# AT32F437.net
KiCad netlist of a schematic drawn in EasyEDA
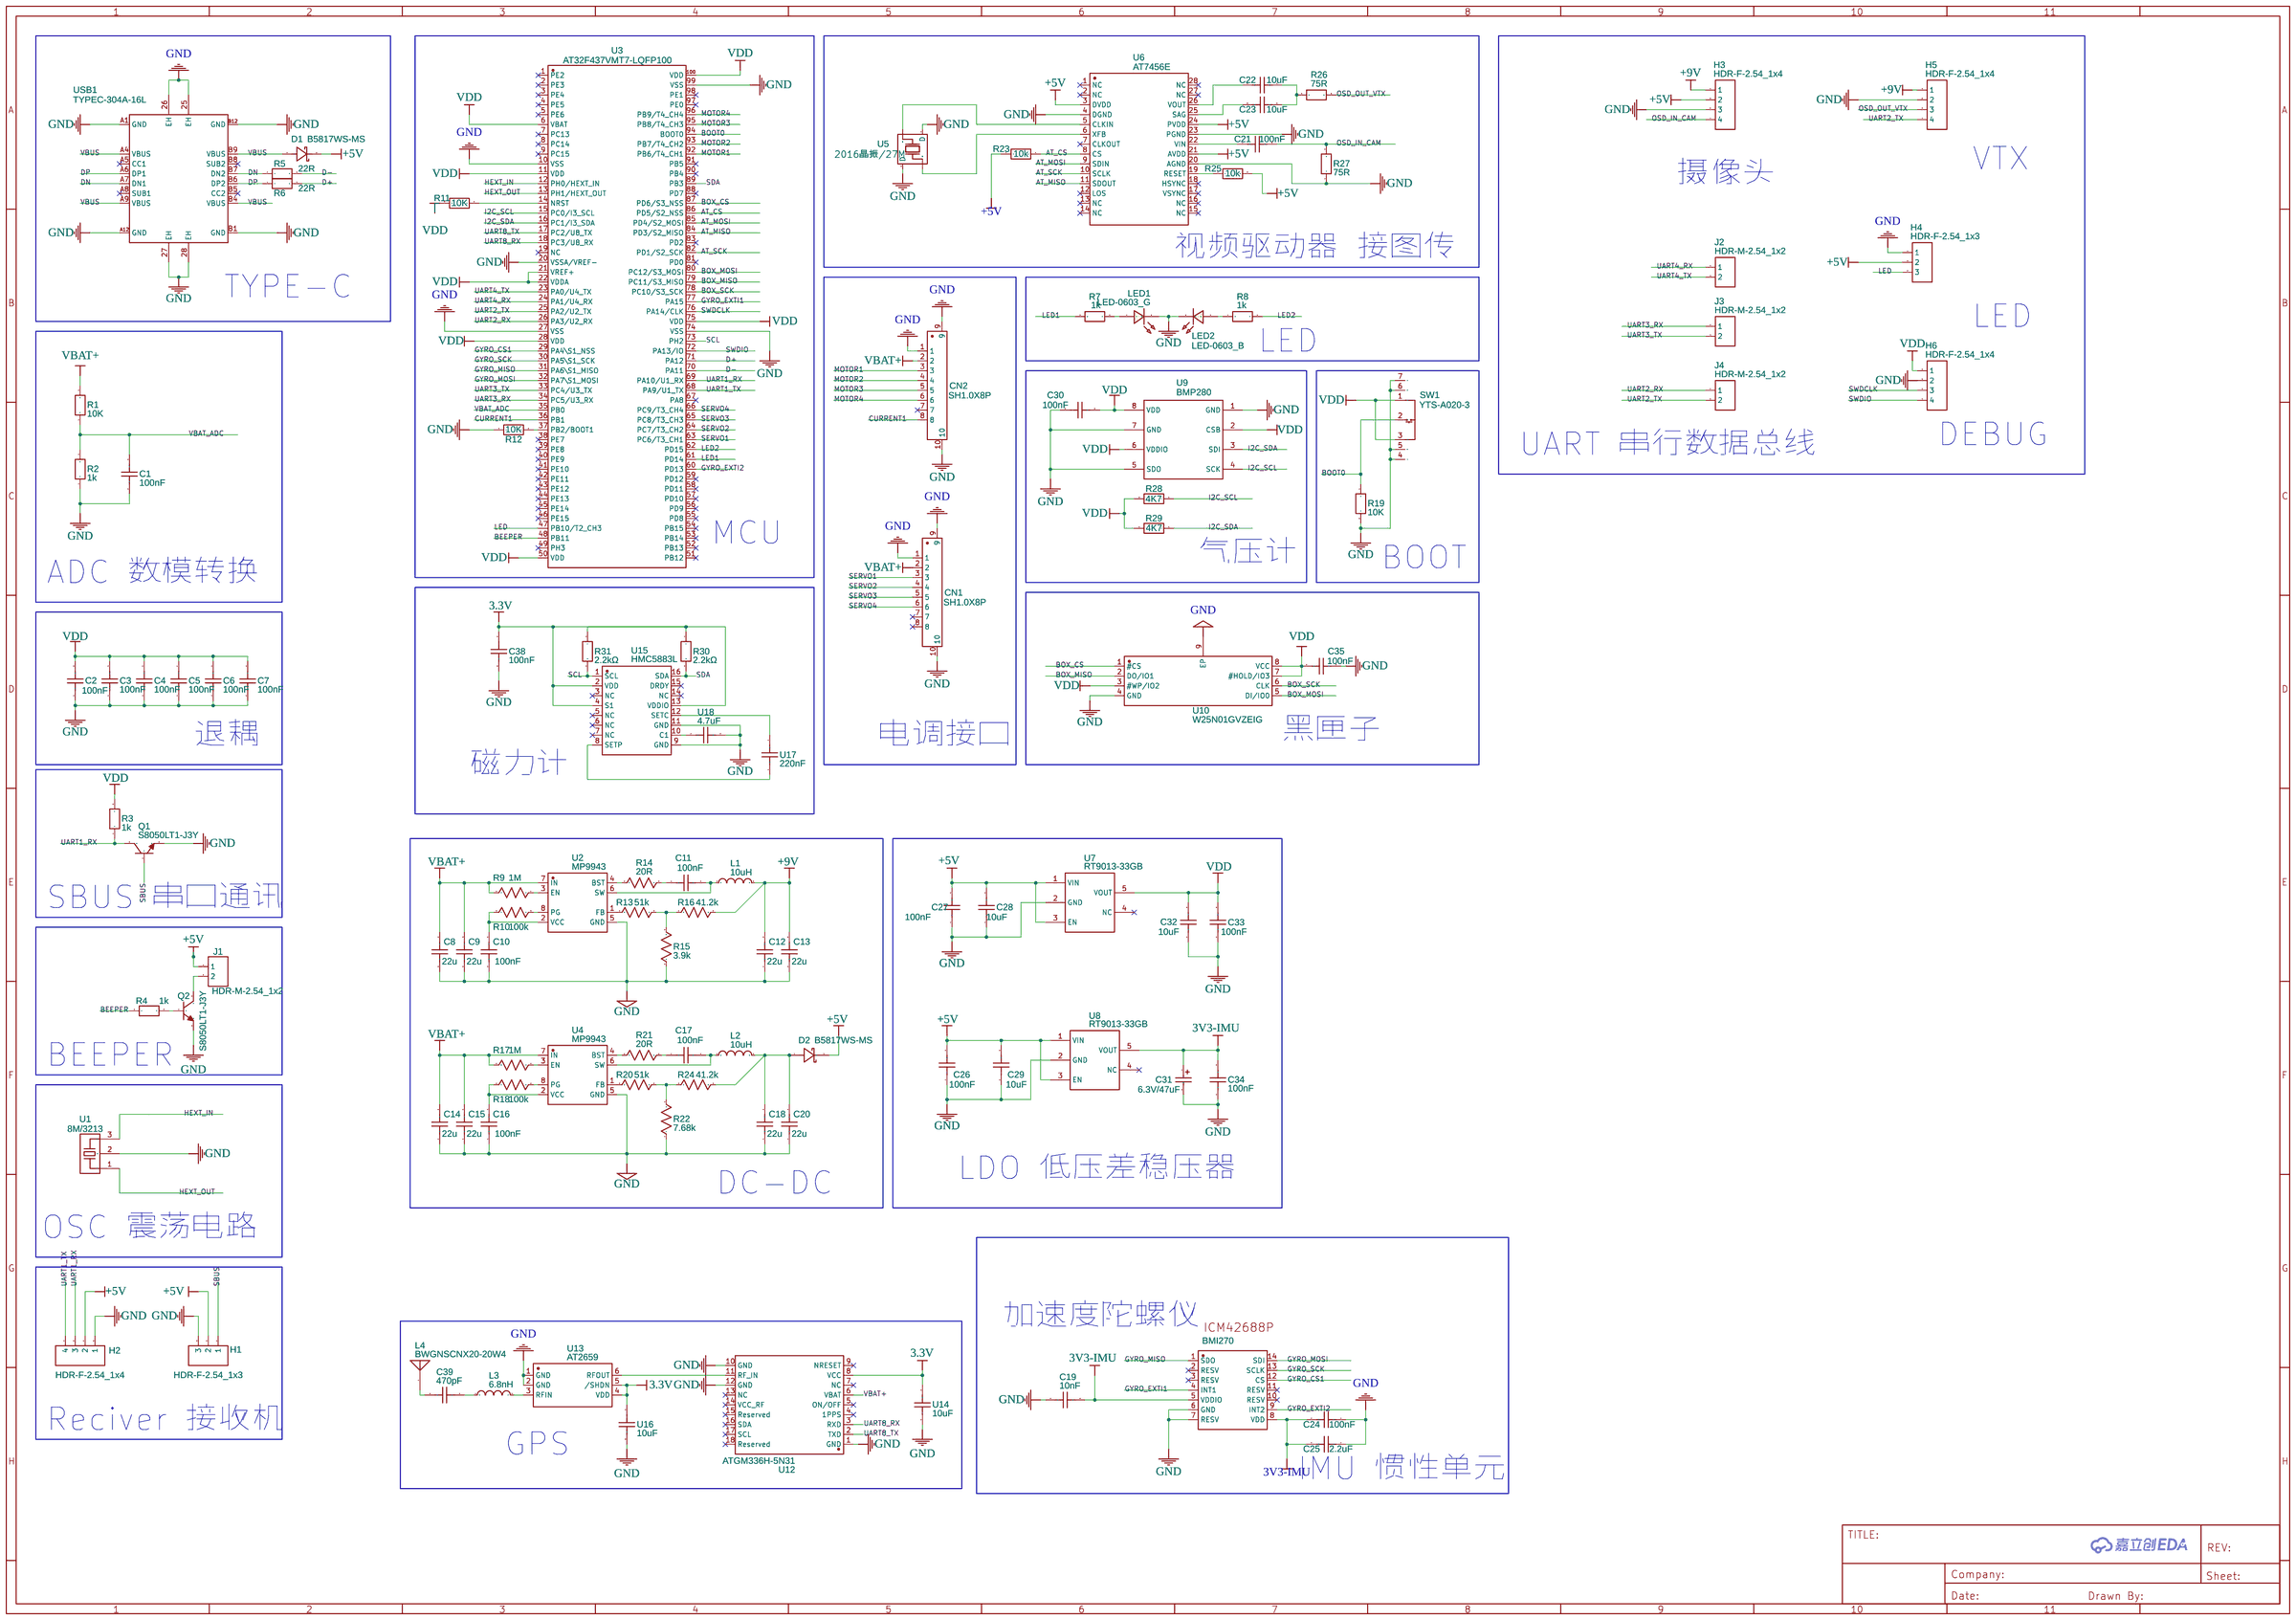
[diagram p0: schematic sheet]

(export (version "E")
  (design (tool "Eeschema 10.0.6"))
  (components
    (comp (ref "C1") (value "100nF") (libsource (lib "") (part "C_0402_US_1")))
    (comp (ref "C2") (value "100nF") (libsource (lib "") (part "C_0402_US_1")))
    (comp (ref "C3") (value "100nF") (libsource (lib "") (part "C_0402_US_1")))
    (comp (ref "C4") (value "100nF") (libsource (lib "") (part "C_0402_US_1")))
    (comp (ref "C5") (value "100nF") (libsource (lib "") (part "C_0402_US_1")))
    (comp (ref "C6") (value "100nF") (libsource (lib "") (part "C_0402_US_1")))
    (comp (ref "C7") (value "100nF") (libsource (lib "") (part "C_0402_US_1")))
    (comp (ref "C8") (value "22u") (libsource (lib "") (part "C_0201_US")))
    (comp (ref "C9") (value "22u") (libsource (lib "") (part "C_0201_US")))
    (comp (ref "C10") (value "100nF") (libsource (lib "") (part "C_0201_US")))
    (comp (ref "C11") (value "100nF") (libsource (lib "") (part "C_0201_US_1")))
    (comp (ref "C12") (value "22u") (libsource (lib "") (part "C_0201_US")))
    (comp (ref "C13") (value "22u") (libsource (lib "") (part "C_0201_US")))
    (comp (ref "C14") (value "22u") (libsource (lib "") (part "C_0201_US")))
    (comp (ref "C15") (value "22u") (libsource (lib "") (part "C_0201_US")))
    (comp (ref "C16") (value "100nF") (libsource (lib "") (part "C_0201_US")))
    (comp (ref "C17") (value "100nF") (libsource (lib "") (part "C_0201_US_1")))
    (comp (ref "C18") (value "22u") (libsource (lib "") (part "C_0201_US")))
    (comp (ref "C19") (value "10nF") (libsource (lib "") (part "C_0402_US_2")))
    (comp (ref "C20") (value "22u") (libsource (lib "") (part "C_0201_US")))
    (comp (ref "C21") (value "100nF") (libsource (lib "") (part "C_0402_US_2")))
    (comp (ref "C22") (value "10uF") (libsource (lib "") (part "C_0603_US")))
    (comp (ref "C23") (value "10uF") (libsource (lib "") (part "C_0603_US")))
    (comp (ref "C24") (value "100nF") (libsource (lib "") (part "C_0402_US")))
    (comp (ref "C25") (value "2.2uF") (libsource (lib "") (part "C_0402_US")))
    (comp (ref "C26") (value "100nF") (libsource (lib "") (part "C_0603_US_1")))
    (comp (ref "C27") (value "100nF") (libsource (lib "") (part "C_0603_US_1")))
    (comp (ref "C28") (value "10uF") (libsource (lib "") (part "C_0603_US_1")))
    (comp (ref "C29") (value "10uF") (libsource (lib "") (part "C_0402_US_1")))
    (comp (ref "C30") (value "100nF") (libsource (lib "") (part "C_0402_US_2")))
    (comp (ref "C31")
      (value "6.3V/47uF")
      (fields (field (name "Manufacturer Part") "TAJA476K006RNJ") (field (name "Manufacturer") "AVX"))
      (libsource (lib "") (part "TAJA476K006RNJ"))
    )
    (comp (ref "C32") (value "10uF") (libsource (lib "") (part "C_0603_US_1")))
    (comp (ref "C33") (value "100nF") (libsource (lib "") (part "C_0603_US_1")))
    (comp (ref "C34") (value "100nF") (libsource (lib "") (part "C_0402_US_1")))
    (comp (ref "C35") (value "100nF") (libsource (lib "") (part "C_0402_US_2")))
    (comp (ref "C38")
      (value "100nF")
      (fields
        (field (name "Manufacturer Part") "CC0603MRY5V8BB104")
        (field (name "Manufacturer") "YAGEO(国巨)")
      )
      (libsource (lib "") (part "CC0603MRY5V8BB104"))
    )
    (comp (ref "C39")
      (value "470pF")
      (fields (field (name "Manufacturer Part") "FM18X471K101PSG") (field (name "Manufacturer") "PSA(信昌电陶)"))
      (libsource (lib "") (part "FM18X471K101PSG"))
    )
    (comp (ref "CN1")
      (value "SH1.0X8P")
      (fields (field (name "Manufacturer Part") "WAFER_SMT_1.0X8"))
      (libsource (lib "") (part "WAFER_SMT_1.0X8"))
    )
    (comp (ref "CN2")
      (value "SH1.0X8P")
      (fields (field (name "Manufacturer Part") "WAFER_SMT_1.0X8"))
      (libsource (lib "") (part "WAFER_SMT_1.0X8"))
    )
    (comp (ref "D1")
      (value "B5817WS-MS")
      (fields (field (name "Manufacturer") "MSKSEMI(美森科)"))
      (libsource (lib "") (part "B5817WS-MS"))
    )
    (comp (ref "D2")
      (value "B5817WS-MS")
      (fields (field (name "Manufacturer") "MSKSEMI(美森科)"))
      (libsource (lib "") (part "B5817WS-MS"))
    )
    (comp (ref "H1") (value "HDR-F-2.54_1x3") (libsource (lib "") (part "HDR-F-2.54_1x3")))
    (comp (ref "H2") (value "HDR-F-2.54_1x4") (libsource (lib "") (part "HDR-F-2.54_1x4")))
    (comp (ref "H3") (value "HDR-F-2.54_1x4") (libsource (lib "") (part "HDR-F-2.54_1x4_1")))
    (comp (ref "H4") (value "HDR-F-2.54_1x3") (libsource (lib "") (part "HDR-F-2.54_1x3_1")))
    (comp (ref "H5") (value "HDR-F-2.54_1x4") (libsource (lib "") (part "HDR-F-2.54_1x4_1")))
    (comp (ref "H6") (value "HDR-F-2.54_1x4") (libsource (lib "") (part "HDR-F-2.54_1x4_1")))
    (comp (ref "J1") (value "HDR-M-2.54_1x2") (libsource (lib "") (part "HDR-M-2.54_1x2")))
    (comp (ref "J2") (value "HDR-M-2.54_1x2") (libsource (lib "") (part "HDR-M-2.54_1x2")))
    (comp (ref "J3") (value "HDR-M-2.54_1x2") (libsource (lib "") (part "HDR-M-2.54_1x2")))
    (comp (ref "J4") (value "HDR-M-2.54_1x2") (libsource (lib "") (part "HDR-M-2.54_1x2")))
    (comp (ref "L1")
      (value "10uH")
      (fields (field (name "Manufacturer Part") "PHC0420-100M-T") (field (name "Manufacturer") "EMTEK"))
      (libsource (lib "") (part "PHC0420-100M-T"))
    )
    (comp (ref "L2")
      (value "10uH")
      (fields (field (name "Manufacturer Part") "PHC0420-100M-T") (field (name "Manufacturer") "EMTEK"))
      (libsource (lib "") (part "PHC0420-100M-T"))
    )
    (comp (ref "L3")
      (value "6.8nH")
      (fields (field (name "Manufacturer Part") "VHF060303H6N8KT") (field (name "Manufacturer") "FH(风华)"))
      (libsource (lib "") (part "VHF060303H6N8KT"))
    )
    (comp (ref "L4")
      (value "BWGNSCNX20-20W4")
      (fields (field (name "Manufacturer") "BAT WIRELESS(蝙蝠无线)"))
      (libsource (lib "") (part "BWGNSCNX20-20W4"))
    )
    (comp (ref "LED1")
      (value "LED-0603_G")
      (fields
        (field (name "Manufacturer Part") "19-217/GHC-YR1S2/3T")
        (field (name "Manufacturer") "EVERLIGHT(台湾亿光)")
      )
      (libsource (lib "") (part "LED-0603_G"))
    )
    (comp (ref "LED2")
      (value "LED-0603_B")
      (fields
        (field (name "Manufacturer Part") "19-217/BHC-ZL1M2RY/3T")
        (field (name "Manufacturer") "EVERLIGHT(台湾亿光)")
      )
      (libsource (lib "") (part "LED-0603_B"))
    )
    (comp (ref "Q1")
      (value "S8050LT1-J3Y")
      (fields (field (name "Manufacturer") "FH(风华)"))
      (libsource (lib "") (part "S8050LT1-J3Y_1"))
    )
    (comp (ref "Q2")
      (value "S8050LT1-J3Y")
      (fields (field (name "Manufacturer") "FH(风华)"))
      (libsource (lib "") (part "S8050LT1-J3Y"))
    )
    (comp (ref "R1") (value "10K") (libsource (lib "") (part "R_0603_EU_2")))
    (comp (ref "R2") (value "1k") (libsource (lib "") (part "R_0603_EU_2")))
    (comp (ref "R3") (value "1k") (libsource (lib "") (part "R_0402_EU_2")))
    (comp (ref "R4") (value "1k") (libsource (lib "") (part "R_0402_EU")))
    (comp (ref "R5") (value "22R") (libsource (lib "") (part "R_0402_EU")))
    (comp (ref "R6") (value "22R") (libsource (lib "") (part "R_0402_EU")))
    (comp (ref "R7") (value "1k") (libsource (lib "") (part "R_0603_EU")))
    (comp (ref "R8") (value "1k") (libsource (lib "") (part "R_0603_EU_3")))
    (comp (ref "R9") (value "1M") (libsource (lib "") (part "R_0201_US_2")))
    (comp (ref "R10") (value "100k") (libsource (lib "") (part "R_0201_US")))
    (comp (ref "R11") (value "10K") (libsource (lib "") (part "R_0603_EU")))
    (comp (ref "R12") (value "10K") (libsource (lib "") (part "R_0603_EU_3")))
    (comp (ref "R13") (value "51k") (libsource (lib "") (part "R_0201_US")))
    (comp (ref "R14") (value "20R") (libsource (lib "") (part "R_0201_US")))
    (comp (ref "R15") (value "3.9k") (libsource (lib "") (part "R_0201_US_1")))
    (comp (ref "R16") (value "41.2k") (libsource (lib "") (part "R_0201_US")))
    (comp (ref "R17") (value "1M") (libsource (lib "") (part "R_0201_US_2")))
    (comp (ref "R18") (value "100k") (libsource (lib "") (part "R_0201_US")))
    (comp (ref "R19") (value "10K") (libsource (lib "") (part "R_0603_EU_1")))
    (comp (ref "R20") (value "51k") (libsource (lib "") (part "R_0201_US")))
    (comp (ref "R21") (value "20R") (libsource (lib "") (part "R_0201_US")))
    (comp (ref "R22") (value "7.68k") (libsource (lib "") (part "R_0201_US_1")))
    (comp (ref "R23") (value "10k") (libsource (lib "") (part "R_0402_EU")))
    (comp (ref "R24") (value "41.2k") (libsource (lib "") (part "R_0201_US")))
    (comp (ref "R25") (value "10k") (libsource (lib "") (part "R_0402_EU")))
    (comp (ref "R26") (value "75R") (libsource (lib "") (part "R_0805_EU")))
    (comp (ref "R27") (value "75R") (libsource (lib "") (part "R_0805_EU_1")))
    (comp (ref "R28") (value "4K7") (libsource (lib "") (part "R_0402_EU_1")))
    (comp (ref "R29") (value "4K7") (libsource (lib "") (part "R_0402_EU_1")))
    (comp (ref "R30")
      (value "2.2kΩ")
      (fields (field (name "Manufacturer Part") "SCR0603J2K2") (field (name "Manufacturer") "VO(翔胜)"))
      (libsource (lib "") (part "SCR0603J2K2"))
    )
    (comp (ref "R31")
      (value "2.2kΩ")
      (fields (field (name "Manufacturer Part") "SCR0603J2K2") (field (name "Manufacturer") "VO(翔胜)"))
      (libsource (lib "") (part "SCR0603J2K2"))
    )
    (comp (ref "SDO1") (value "BMI270") (libsource (lib "") (part "ICM42688-P")))
    (comp (ref "SW1")
      (value "YTS-A020-3")
      (fields (field (name "Manufacturer") "YIYUAN(怡远)"))
      (libsource (lib "") (part "YTS-A020-3"))
    )
    (comp (ref "U1") (value "8M/3213") (libsource (lib "") (part "3213晶振")))
    (comp (ref "U2") (value "MP9943") (libsource (lib "") (part "MP9943")))
    (comp (ref "U3")
      (value "AT32F437VMT7-LQFP100")
      (fields (field (name "Manufacturer Part") "AT32F435VMT7") (field (name "Manufacturer") "ARTERY（雅特力）"))
      (libsource (lib "") (part "AT32F435VGT7"))
    )
    (comp (ref "U4") (value "MP9943") (libsource (lib "") (part "MP9943")))
    (comp (ref "U5") (value "2016晶振/27M") (libsource (lib "") (part "3225晶振")))
    (comp (ref "U6")
      (value "AT7456E")
      (fields (field (name "Manufacturer") "ZHONGKEWEI"))
      (libsource (lib "") (part "AT7456E"))
    )
    (comp (ref "U7")
      (value "RT9013-33GB")
      (fields (field (name "Manufacturer") "RICHTEK"))
      (libsource (lib "") (part "RT9013-33GB"))
    )
    (comp (ref "U8")
      (value "RT9013-33GB")
      (fields (field (name "Manufacturer") "RICHTEK"))
      (libsource (lib "") (part "RT9013-33GB"))
    )
    (comp (ref "U9")
      (value "BMP280")
      (fields (field (name "Manufacturer") "Bosch"))
      (libsource (lib "") (part "BMP280"))
    )
    (comp (ref "U10")
      (value "W25N01GVZEIG")
      (fields (field (name "Manufacturer") "Winbond Elec"))
      (libsource (lib "") (part "W25N01GVZEIG NoHole"))
    )
    (comp (ref "U12")
      (value "ATGM336H-5N31")
      (fields (field (name "Manufacturer") "杭州中科微"))
      (libsource (lib "") (part "ATGM336H-5N31"))
    )
    (comp (ref "U13")
      (value "AT2659")
      (fields (field (name "Manufacturer") "杭州中科微"))
      (libsource (lib "") (part "AT2659"))
    )
    (comp (ref "U14")
      (value "10uF")
      (fields (field (name "Manufacturer Part") "0603X106K100CT") (field (name "Manufacturer") "Walsin(华新科)"))
      (libsource (lib "") (part "0603X106K100CT"))
    )
    (comp (ref "U15") (value "HMC5883L") (libsource (lib "") (part "HMC5883L")))
    (comp (ref "U16")
      (value "10uF")
      (fields (field (name "Manufacturer Part") "0603X106K100CT") (field (name "Manufacturer") "Walsin(华新科)"))
      (libsource (lib "") (part "0603X106K100CT"))
    )
    (comp (ref "U17")
      (value "220nF")
      (fields (field (name "Manufacturer Part") "CGA3E3X5R1V224M080AB") (field (name "Manufacturer") "TDK"))
      (libsource (lib "") (part "CGA3E3X5R1V224M080AB"))
    )
    (comp (ref "U18")
      (value "4.7uF")
      (fields (field (name "Manufacturer Part") "C1005X5R1A475M050BC") (field (name "Manufacturer") "TDK"))
      (libsource (lib "") (part "C1005X5R1A475M050BC"))
    )
    (comp (ref "USB1")
      (value "TYPEC-304A-16L")
      (fields
        (field (name "Manufacturer Part") "TYPEC-304A-ACP16L")
        (field (name "Manufacturer") "XUNPU(讯普)")
      )
      (libsource (lib "") (part "TYPEC-304A-ACP16L"))
    )
  )
  (nets
    (net (code "1") (name "+5V") (class "Default")
      (node (ref "C26") (pin "2") (pinfunction "2_2") (pintype "unspecified"))
      (node (ref "C27") (pin "2") (pinfunction "2_2") (pintype "unspecified"))
      (node (ref "C28") (pin "2") (pinfunction "2_2") (pintype "unspecified"))
      (node (ref "C29") (pin "2") (pinfunction "2_2") (pintype "unspecified"))
      (node (ref "D1") (pin "2") (pinfunction "K_2") (pintype "unspecified"))
      (node (ref "D2") (pin "2") (pinfunction "K_2") (pintype "unspecified"))
      (node (ref "H1") (pin "2") (pinfunction "2_2") (pintype "input"))
      (node (ref "H2") (pin "2") (pinfunction "2_2") (pintype "unspecified"))
      (node (ref "H3") (pin "2") (pinfunction "2_2") (pintype "unspecified"))
      (node (ref "H4") (pin "2") (pinfunction "2_2") (pintype "input"))
      (node (ref "J1") (pin "1") (pinfunction "1_1") (pintype "unspecified"))
      (node (ref "R23") (pin "1") (pinfunction "1_1") (pintype "unspecified"))
      (node (ref "R25") (pin "2") (pinfunction "2_2") (pintype "unspecified"))
      (node (ref "U6") (pin "21") (pinfunction "AVDD_21") (pintype "unspecified"))
      (node (ref "U6") (pin "24") (pinfunction "PVDD_24") (pintype "unspecified"))
      (node (ref "U6") (pin "3") (pinfunction "DVDD_3") (pintype "unspecified"))
      (node (ref "U7") (pin "1") (pinfunction "VIN_1") (pintype "unspecified"))
      (node (ref "U7") (pin "3") (pinfunction "EN_3") (pintype "unspecified"))
      (node (ref "U8") (pin "1") (pinfunction "VIN_1") (pintype "unspecified"))
      (node (ref "U8") (pin "3") (pinfunction "EN_3") (pintype "unspecified"))
    )
    (net (code "2") (name "+9V") (class "Default")
      (node (ref "C12") (pin "2") (pinfunction "2_2") (pintype "unspecified"))
      (node (ref "C13") (pin "2") (pinfunction "2_2") (pintype "unspecified"))
      (node (ref "H3") (pin "1") (pinfunction "1_1") (pintype "unspecified"))
      (node (ref "H5") (pin "1") (pinfunction "1_1") (pintype "unspecified"))
      (node (ref "L1") (pin "2") (pinfunction "2_2") (pintype "unspecified"))
      (node (ref "R16") (pin "2") (pinfunction "2_2") (pintype "unspecified"))
    )
    (net (code "3") (name "/AT_CS") (class "Default")
      (node (ref "R23") (pin "2") (pinfunction "2_2") (pintype "unspecified"))
      (node (ref "U3") (pin "86") (pinfunction "PD5/S2_NSS_86") (pintype "unspecified"))
      (node (ref "U6") (pin "8") (pinfunction "CS_8") (pintype "unspecified"))
    )
    (net (code "4") (name "/AT_MISO") (class "Default")
      (node (ref "U3") (pin "84") (pinfunction "PD3/S2_MISO_84") (pintype "unspecified"))
      (node (ref "U6") (pin "11") (pinfunction "SDOUT_11") (pintype "unspecified"))
    )
    (net (code "5") (name "/AT_MOSI") (class "Default")
      (node (ref "U3") (pin "85") (pinfunction "PD4/S2_MOSI_85") (pintype "unspecified"))
      (node (ref "U6") (pin "9") (pinfunction "SDIN_9") (pintype "unspecified"))
    )
    (net (code "6") (name "/AT_SCK") (class "Default")
      (node (ref "U3") (pin "82") (pinfunction "PD1/S2_SCK_82") (pintype "unspecified"))
      (node (ref "U6") (pin "10") (pinfunction "SCLK_10") (pintype "unspecified"))
    )
    (net (code "7") (name "/BEEPER") (class "Default")
      (node (ref "R4") (pin "1") (pinfunction "1_1") (pintype "unspecified"))
      (node (ref "U3") (pin "48") (pinfunction "PB11_48") (pintype "unspecified"))
    )
    (net (code "8") (name "/BOOT0") (class "Default")
      (node (ref "R19") (pin "1") (pinfunction "1_1") (pintype "unspecified"))
      (node (ref "SW1") (pin "2") (pinfunction "2_2") (pintype "unspecified"))
      (node (ref "U3") (pin "94") (pinfunction "BOOT0_94") (pintype "unspecified"))
    )
    (net (code "9") (name "/BOX_CS") (class "Default")
      (node (ref "U10") (pin "1") (pinfunction "#CS_1") (pintype "unspecified"))
      (node (ref "U3") (pin "87") (pinfunction "PD6/S3_NSS_87") (pintype "unspecified"))
    )
    (net (code "10") (name "/BOX_MISO") (class "Default")
      (node (ref "U10") (pin "2") (pinfunction "DO/IO1_2") (pintype "unspecified"))
      (node (ref "U3") (pin "79") (pinfunction "PC11/S3_MISO_79") (pintype "unspecified"))
    )
    (net (code "11") (name "/BOX_MOSI") (class "Default")
      (node (ref "U10") (pin "5") (pinfunction "DI/IO0_5") (pintype "unspecified"))
      (node (ref "U3") (pin "80") (pinfunction "PC12/S3_MOSI_80") (pintype "unspecified"))
    )
    (net (code "12") (name "/BOX_SCK") (class "Default")
      (node (ref "U10") (pin "6") (pinfunction "CLK_6") (pintype "unspecified"))
      (node (ref "U3") (pin "78") (pinfunction "PC10/S3_SCK_78") (pintype "unspecified"))
    )
    (net (code "13") (name "/CURRENT1") (class "Default")
      (node (ref "CN2") (pin "8") (pinfunction "8_8") (pintype "unspecified"))
      (node (ref "U3") (pin "36") (pinfunction "PB1_36") (pintype "unspecified"))
    )
    (net (code "14") (name "/D+") (class "Default")
      (node (ref "R6") (pin "2") (pinfunction "2_2") (pintype "unspecified"))
      (node (ref "U3") (pin "71") (pinfunction "PA12_71") (pintype "unspecified"))
    )
    (net (code "15") (name "/D-") (class "Default")
      (node (ref "R5") (pin "2") (pinfunction "2_2") (pintype "unspecified"))
      (node (ref "U3") (pin "70") (pinfunction "PA11_70") (pintype "unspecified"))
    )
    (net (code "16") (name "/DN") (class "Default")
      (node (ref "R5") (pin "1") (pinfunction "1_1") (pintype "unspecified"))
      (node (ref "USB1") (pin "A7") (pinfunction "DN1_A7") (pintype "unspecified"))
      (node (ref "USB1") (pin "B7") (pinfunction "DN2_B7") (pintype "unspecified"))
    )
    (net (code "17") (name "/DP") (class "Default")
      (node (ref "R6") (pin "1") (pinfunction "1_1") (pintype "unspecified"))
      (node (ref "USB1") (pin "A6") (pinfunction "DP1_A6") (pintype "unspecified"))
      (node (ref "USB1") (pin "B6") (pinfunction "DP2_B6") (pintype "unspecified"))
    )
    (net (code "18") (name "/GYRO_CS1") (class "Default")
      (node (ref "SDO1") (pin "12") (pinfunction "CS_12") (pintype "unspecified"))
      (node (ref "U3") (pin "29") (pinfunction "PA4\\S1_NSS_29") (pintype "unspecified"))
    )
    (net (code "19") (name "/GYRO_EXTI1") (class "Default")
      (node (ref "SDO1") (pin "4") (pinfunction "INT1_4") (pintype "unspecified"))
      (node (ref "U3") (pin "77") (pinfunction "PA15_77") (pintype "unspecified"))
    )
    (net (code "20") (name "/GYRO_EXTI2") (class "Default")
      (node (ref "SDO1") (pin "9") (pinfunction "INT2_9") (pintype "unspecified"))
      (node (ref "U3") (pin "60") (pinfunction "PD13_60") (pintype "unspecified"))
    )
    (net (code "21") (name "/GYRO_MISO") (class "Default")
      (node (ref "SDO1") (pin "1") (pinfunction "SDO_1") (pintype "unspecified"))
      (node (ref "U3") (pin "31") (pinfunction "PA6\\S1_MISO_31") (pintype "unspecified"))
    )
    (net (code "22") (name "/GYRO_MOSI") (class "Default")
      (node (ref "SDO1") (pin "14") (pinfunction "SDI_14") (pintype "unspecified"))
      (node (ref "U3") (pin "32") (pinfunction "PA7\\S1_MOSI_32") (pintype "unspecified"))
    )
    (net (code "23") (name "/GYRO_SCK") (class "Default")
      (node (ref "SDO1") (pin "13") (pinfunction "SCLK_13") (pintype "unspecified"))
      (node (ref "U3") (pin "30") (pinfunction "PA5\\S1_SCK_30") (pintype "unspecified"))
    )
    (net (code "24") (name "/HEXT_IN") (class "Default")
      (node (ref "U1") (pin "3") (pinfunction "3_3") (pintype "unspecified"))
      (node (ref "U3") (pin "12") (pinfunction "PH0/HEXT_IN_12") (pintype "unspecified"))
    )
    (net (code "25") (name "/HEXT_OUT") (class "Default")
      (node (ref "U1") (pin "1") (pinfunction "1_1") (pintype "unspecified"))
      (node (ref "U3") (pin "13") (pinfunction "PH1/HEXT_OUT_13") (pintype "unspecified"))
    )
    (net (code "26") (name "/I2C_SCL") (class "Default")
      (node (ref "R28") (pin "1") (pinfunction "1_1") (pintype "unspecified"))
      (node (ref "U3") (pin "15") (pinfunction "PC0/I3_SCL_15") (pintype "unspecified"))
      (node (ref "U9") (pin "4") (pinfunction "SCK_4") (pintype "unspecified"))
    )
    (net (code "27") (name "/I2C_SDA") (class "Default")
      (node (ref "R29") (pin "1") (pinfunction "1_1") (pintype "unspecified"))
      (node (ref "U3") (pin "16") (pinfunction "PC1/I3_SDA_16") (pintype "unspecified"))
      (node (ref "U9") (pin "3") (pinfunction "SDI_3") (pintype "unspecified"))
    )
    (net (code "28") (name "/LED") (class "Default")
      (node (ref "H4") (pin "3") (pinfunction "3_3") (pintype "input"))
      (node (ref "U3") (pin "47") (pinfunction "PB10/T2_CH3_47") (pintype "unspecified"))
    )
    (net (code "29") (name "/LED1") (class "Default")
      (node (ref "R7") (pin "2") (pinfunction "2_2") (pintype "unspecified"))
      (node (ref "U3") (pin "61") (pinfunction "PD14_61") (pintype "unspecified"))
    )
    (net (code "30") (name "/LED2") (class "Default")
      (node (ref "R8") (pin "2") (pinfunction "2_2") (pintype "unspecified"))
      (node (ref "U3") (pin "62") (pinfunction "PD15_62") (pintype "unspecified"))
    )
    (net (code "31") (name "/MOTOR1") (class "Default")
      (node (ref "CN2") (pin "3") (pinfunction "3_3") (pintype "unspecified"))
      (node (ref "U3") (pin "92") (pinfunction "PB6/T4_CH1_92") (pintype "unspecified"))
    )
    (net (code "32") (name "/MOTOR2") (class "Default")
      (node (ref "CN2") (pin "4") (pinfunction "4_4") (pintype "unspecified"))
      (node (ref "U3") (pin "93") (pinfunction "PB7/T4_CH2_93") (pintype "unspecified"))
    )
    (net (code "33") (name "/MOTOR3") (class "Default")
      (node (ref "CN2") (pin "5") (pinfunction "5_5") (pintype "unspecified"))
      (node (ref "U3") (pin "95") (pinfunction "PB8/T4_CH3_95") (pintype "unspecified"))
    )
    (net (code "34") (name "/MOTOR4") (class "Default")
      (node (ref "CN2") (pin "6") (pinfunction "6_6") (pintype "unspecified"))
      (node (ref "U3") (pin "96") (pinfunction "PB9/T4_CH4_96") (pintype "unspecified"))
    )
    (net (code "35") (name "/OSD_IN_CAM") (class "Default")
      (node (ref "C21") (pin "2") (pinfunction "2_2") (pintype "unspecified"))
      (node (ref "H3") (pin "4") (pinfunction "4_4") (pintype "unspecified"))
      (node (ref "R27") (pin "2") (pinfunction "2_2") (pintype "unspecified"))
    )
    (net (code "36") (name "/OSD_OUT_VTX") (class "Default")
      (node (ref "H5") (pin "3") (pinfunction "3_3") (pintype "unspecified"))
      (node (ref "R26") (pin "2") (pinfunction "2_2") (pintype "unspecified"))
    )
    (net (code "37") (name "/SBUS") (class "Default")
      (node (ref "H1") (pin "1") (pinfunction "1_1") (pintype "input"))
      (node (ref "Q1") (pin "1") (pinfunction "1_1") (pintype "input"))
    )
    (net (code "38") (name "/SCL") (class "Default")
      (node (ref "R31") (pin "2") (pinfunction "2_2") (pintype "unspecified"))
      (node (ref "U15") (pin "1") (pinfunction "SCL_1") (pintype "unspecified"))
      (node (ref "U3") (pin "73") (pinfunction "PH2_73") (pintype "unspecified"))
    )
    (net (code "39") (name "/SDA") (class "Default")
      (node (ref "R30") (pin "2") (pinfunction "2_2") (pintype "unspecified"))
      (node (ref "U15") (pin "16") (pinfunction "SDA_16") (pintype "unspecified"))
      (node (ref "U3") (pin "89") (pinfunction "PB3_89") (pintype "unspecified"))
    )
    (net (code "40") (name "/SERVO1") (class "Default")
      (node (ref "CN1") (pin "3") (pinfunction "3_3") (pintype "unspecified"))
      (node (ref "U3") (pin "63") (pinfunction "PC6/T3_CH1_63") (pintype "unspecified"))
    )
    (net (code "41") (name "/SERVO2") (class "Default")
      (node (ref "CN1") (pin "4") (pinfunction "4_4") (pintype "unspecified"))
      (node (ref "U3") (pin "64") (pinfunction "PC7/T3_CH2_64") (pintype "unspecified"))
    )
    (net (code "42") (name "/SERVO3") (class "Default")
      (node (ref "CN1") (pin "5") (pinfunction "5_5") (pintype "unspecified"))
      (node (ref "U3") (pin "65") (pinfunction "PC8/T3_CH3_65") (pintype "unspecified"))
    )
    (net (code "43") (name "/SERVO4") (class "Default")
      (node (ref "CN1") (pin "6") (pinfunction "6_6") (pintype "unspecified"))
      (node (ref "U3") (pin "66") (pinfunction "PC9/T3_CH4_66") (pintype "unspecified"))
    )
    (net (code "44") (name "/SWDCLK") (class "Default")
      (node (ref "H6") (pin "3") (pinfunction "3_3") (pintype "unspecified"))
      (node (ref "U3") (pin "76") (pinfunction "PA14/CLK_76") (pintype "unspecified"))
    )
    (net (code "45") (name "/SWDIO") (class "Default")
      (node (ref "H6") (pin "4") (pinfunction "4_4") (pintype "unspecified"))
      (node (ref "U3") (pin "72") (pinfunction "PA13/IO_72") (pintype "unspecified"))
    )
    (net (code "46") (name "/UART1_RX") (class "Default")
      (node (ref "H2") (pin "3") (pinfunction "3_3") (pintype "unspecified"))
      (node (ref "Q1") (pin "3") (pinfunction "3_3") (pintype "input"))
      (node (ref "R3") (pin "1") (pinfunction "1_1") (pintype "unspecified"))
      (node (ref "U3") (pin "69") (pinfunction "PA10/U1_RX_69") (pintype "unspecified"))
    )
    (net (code "47") (name "/UART1_TX") (class "Default")
      (node (ref "H2") (pin "4") (pinfunction "4_4") (pintype "unspecified"))
      (node (ref "U3") (pin "68") (pinfunction "PA9/U1_TX_68") (pintype "unspecified"))
    )
    (net (code "48") (name "/UART2_RX") (class "Default")
      (node (ref "J4") (pin "1") (pinfunction "1_1") (pintype "unspecified"))
      (node (ref "U3") (pin "26") (pinfunction "PA3/U2_RX_26") (pintype "unspecified"))
    )
    (net (code "49") (name "/UART2_TX") (class "Default")
      (node (ref "H5") (pin "4") (pinfunction "4_4") (pintype "unspecified"))
      (node (ref "J4") (pin "2") (pinfunction "2_2") (pintype "unspecified"))
      (node (ref "U3") (pin "25") (pinfunction "PA2/U2_TX_25") (pintype "unspecified"))
    )
    (net (code "50") (name "/UART3_RX") (class "Default")
      (node (ref "J3") (pin "1") (pinfunction "1_1") (pintype "unspecified"))
      (node (ref "U3") (pin "34") (pinfunction "PC5/U3_RX_34") (pintype "unspecified"))
    )
    (net (code "51") (name "/UART3_TX") (class "Default")
      (node (ref "J3") (pin "2") (pinfunction "2_2") (pintype "unspecified"))
      (node (ref "U3") (pin "33") (pinfunction "PC4/U3_TX_33") (pintype "unspecified"))
    )
    (net (code "52") (name "/UART4_RX") (class "Default")
      (node (ref "J2") (pin "1") (pinfunction "1_1") (pintype "unspecified"))
      (node (ref "U3") (pin "24") (pinfunction "PA1/U4_RX_24") (pintype "unspecified"))
    )
    (net (code "53") (name "/UART4_TX") (class "Default")
      (node (ref "J2") (pin "2") (pinfunction "2_2") (pintype "unspecified"))
      (node (ref "U3") (pin "23") (pinfunction "PA0/U4_TX_23") (pintype "unspecified"))
    )
    (net (code "54") (name "/UART8_RX") (class "Default")
      (node (ref "U12") (pin "3") (pinfunction "RXD_3") (pintype "unspecified"))
      (node (ref "U3") (pin "18") (pinfunction "PC3/U8_RX_18") (pintype "unspecified"))
    )
    (net (code "55") (name "/UART8_TX") (class "Default")
      (node (ref "U12") (pin "2") (pinfunction "TXD_2") (pintype "unspecified"))
      (node (ref "U3") (pin "17") (pinfunction "PC2/U8_TX_17") (pintype "unspecified"))
    )
    (net (code "56") (name "/VBAT_ADC") (class "Default")
      (node (ref "C1") (pin "2") (pinfunction "2_2") (pintype "unspecified"))
      (node (ref "R1") (pin "1") (pinfunction "1_1") (pintype "unspecified"))
      (node (ref "R2") (pin "2") (pinfunction "2_2") (pintype "unspecified"))
      (node (ref "U3") (pin "35") (pinfunction "PB0_35") (pintype "unspecified"))
    )
    (net (code "57") (name "/VBUS") (class "Default")
      (node (ref "D1") (pin "1") (pinfunction "A_1") (pintype "unspecified"))
      (node (ref "USB1") (pin "A4") (pinfunction "VBUS_A4") (pintype "unspecified"))
      (node (ref "USB1") (pin "A9") (pinfunction "VBUS_A9") (pintype "unspecified"))
      (node (ref "USB1") (pin "B4") (pinfunction "VBUS_B4") (pintype "unspecified"))
      (node (ref "USB1") (pin "B9") (pinfunction "VBUS_B9") (pintype "unspecified"))
    )
    (net (code "58") (name "3.3V") (class "Default")
      (node (ref "C38") (pin "1") (pinfunction "1_1") (pintype "unspecified"))
      (node (ref "R30") (pin "1") (pinfunction "1_1") (pintype "unspecified"))
      (node (ref "R31") (pin "1") (pinfunction "1_1") (pintype "unspecified"))
      (node (ref "U12") (pin "8") (pinfunction "VCC_8") (pintype "unspecified"))
      (node (ref "U13") (pin "4") (pinfunction "VDD_4") (pintype "unspecified"))
      (node (ref "U13") (pin "5") (pinfunction "/SHDN_5") (pintype "unspecified"))
      (node (ref "U14") (pin "1") (pinfunction "1_1") (pintype "unspecified"))
      (node (ref "U15") (pin "13") (pinfunction "VDDIO_13") (pintype "unspecified"))
      (node (ref "U15") (pin "2") (pinfunction "VDD_2") (pintype "unspecified"))
      (node (ref "U15") (pin "4") (pinfunction "S1_4") (pintype "unspecified"))
      (node (ref "U16") (pin "1") (pinfunction "1_1") (pintype "unspecified"))
    )
    (net (code "59") (name "3V3-IMU") (class "Default")
      (node (ref "C19") (pin "2") (pinfunction "2_2") (pintype "unspecified"))
      (node (ref "C24") (pin "2") (pinfunction "2_2") (pintype "unspecified"))
      (node (ref "C25") (pin "2") (pinfunction "2_2") (pintype "unspecified"))
      (node (ref "C31") (pin "1") (pinfunction "1_1") (pintype "input"))
      (node (ref "C34") (pin "2") (pinfunction "2_2") (pintype "unspecified"))
      (node (ref "SDO1") (pin "5") (pinfunction "VDDIO_5") (pintype "unspecified"))
      (node (ref "SDO1") (pin "8") (pinfunction "VDD_8") (pintype "unspecified"))
      (node (ref "U8") (pin "5") (pinfunction "VOUT_5") (pintype "unspecified"))
    )
    (net (code "60") (name "GND") (class "Default")
      (node (ref "C1") (pin "1") (pinfunction "1_1") (pintype "unspecified"))
      (node (ref "C10") (pin "1") (pinfunction "1_1") (pintype "unspecified"))
      (node (ref "C12") (pin "1") (pinfunction "1_1") (pintype "unspecified"))
      (node (ref "C13") (pin "1") (pinfunction "1_1") (pintype "unspecified"))
      (node (ref "C14") (pin "1") (pinfunction "1_1") (pintype "unspecified"))
      (node (ref "C15") (pin "1") (pinfunction "1_1") (pintype "unspecified"))
      (node (ref "C16") (pin "1") (pinfunction "1_1") (pintype "unspecified"))
      (node (ref "C18") (pin "1") (pinfunction "1_1") (pintype "unspecified"))
      (node (ref "C19") (pin "1") (pinfunction "1_1") (pintype "unspecified"))
      (node (ref "C2") (pin "1") (pinfunction "1_1") (pintype "unspecified"))
      (node (ref "C20") (pin "1") (pinfunction "1_1") (pintype "unspecified"))
      (node (ref "C24") (pin "1") (pinfunction "1_1") (pintype "unspecified"))
      (node (ref "C25") (pin "1") (pinfunction "1_1") (pintype "unspecified"))
      (node (ref "C26") (pin "1") (pinfunction "1_1") (pintype "unspecified"))
      (node (ref "C27") (pin "1") (pinfunction "1_1") (pintype "unspecified"))
      (node (ref "C28") (pin "1") (pinfunction "1_1") (pintype "unspecified"))
      (node (ref "C29") (pin "1") (pinfunction "1_1") (pintype "unspecified"))
      (node (ref "C3") (pin "1") (pinfunction "1_1") (pintype "unspecified"))
      (node (ref "C30") (pin "1") (pinfunction "1_1") (pintype "unspecified"))
      (node (ref "C31") (pin "2") (pinfunction "2_2") (pintype "input"))
      (node (ref "C32") (pin "1") (pinfunction "1_1") (pintype "unspecified"))
      (node (ref "C33") (pin "1") (pinfunction "1_1") (pintype "unspecified"))
      (node (ref "C34") (pin "1") (pinfunction "1_1") (pintype "unspecified"))
      (node (ref "C35") (pin "2") (pinfunction "2_2") (pintype "unspecified"))
      (node (ref "C38") (pin "2") (pinfunction "2_2") (pintype "unspecified"))
      (node (ref "C4") (pin "1") (pinfunction "1_1") (pintype "unspecified"))
      (node (ref "C5") (pin "1") (pinfunction "1_1") (pintype "unspecified"))
      (node (ref "C6") (pin "1") (pinfunction "1_1") (pintype "unspecified"))
      (node (ref "C7") (pin "1") (pinfunction "1_1") (pintype "unspecified"))
      (node (ref "C8") (pin "1") (pinfunction "1_1") (pintype "unspecified"))
      (node (ref "C9") (pin "1") (pinfunction "1_1") (pintype "unspecified"))
      (node (ref "CN1") (pin "1") (pinfunction "1_1") (pintype "unspecified"))
      (node (ref "CN1") (pin "10") (pinfunction "10_10") (pintype "unspecified"))
      (node (ref "CN1") (pin "9") (pinfunction "9_9") (pintype "unspecified"))
      (node (ref "CN2") (pin "1") (pinfunction "1_1") (pintype "unspecified"))
      (node (ref "CN2") (pin "10") (pinfunction "10_10") (pintype "unspecified"))
      (node (ref "CN2") (pin "9") (pinfunction "9_9") (pintype "unspecified"))
      (node (ref "H1") (pin "3") (pinfunction "3_3") (pintype "input"))
      (node (ref "H2") (pin "1") (pinfunction "1_1") (pintype "unspecified"))
      (node (ref "H3") (pin "3") (pinfunction "3_3") (pintype "unspecified"))
      (node (ref "H4") (pin "1") (pinfunction "1_1") (pintype "input"))
      (node (ref "H5") (pin "2") (pinfunction "2_2") (pintype "unspecified"))
      (node (ref "H6") (pin "2") (pinfunction "2_2") (pintype "unspecified"))
      (node (ref "LED1") (pin "2") (pinfunction "2_2") (pintype "unspecified"))
      (node (ref "LED2") (pin "2") (pinfunction "2_2") (pintype "unspecified"))
      (node (ref "Q1") (pin "2") (pinfunction "2_2") (pintype "input"))
      (node (ref "Q2") (pin "2") (pinfunction "2_2") (pintype "input"))
      (node (ref "R12") (pin "1") (pinfunction "1_1") (pintype "unspecified"))
      (node (ref "R15") (pin "1") (pinfunction "1_1") (pintype "unspecified"))
      (node (ref "R19") (pin "2") (pinfunction "2_2") (pintype "unspecified"))
      (node (ref "R2") (pin "1") (pinfunction "1_1") (pintype "unspecified"))
      (node (ref "R22") (pin "1") (pinfunction "1_1") (pintype "unspecified"))
      (node (ref "R27") (pin "1") (pinfunction "1_1") (pintype "unspecified"))
      (node (ref "SDO1") (pin "6") (pinfunction "GND_6") (pintype "unspecified"))
      (node (ref "SDO1") (pin "7") (pinfunction "RESV_7") (pintype "unspecified"))
      (node (ref "SW1") (pin "4") (pinfunction "4_4") (pintype "unspecified"))
      (node (ref "SW1") (pin "5") (pinfunction "5_5") (pintype "unspecified"))
      (node (ref "SW1") (pin "6") (pinfunction "6_6") (pintype "unspecified"))
      (node (ref "SW1") (pin "7") (pinfunction "7_7") (pintype "unspecified"))
      (node (ref "U1") (pin "2") (pinfunction "2_2") (pintype "unspecified"))
      (node (ref "U10") (pin "4") (pinfunction "GND_4") (pintype "unspecified"))
      (node (ref "U10") (pin "9") (pinfunction "EP_9") (pintype "unspecified"))
      (node (ref "U12") (pin "1") (pinfunction "GND_1") (pintype "unspecified"))
      (node (ref "U12") (pin "10") (pinfunction "GND_10") (pintype "unspecified"))
      (node (ref "U12") (pin "12") (pinfunction "GND_12") (pintype "unspecified"))
      (node (ref "U13") (pin "1") (pinfunction "GND_1") (pintype "unspecified"))
      (node (ref "U13") (pin "2") (pinfunction "GND_2") (pintype "unspecified"))
      (node (ref "U14") (pin "2") (pinfunction "2_2") (pintype "unspecified"))
      (node (ref "U15") (pin "11") (pinfunction "GND_11") (pintype "unspecified"))
      (node (ref "U15") (pin "9") (pinfunction "GND_9") (pintype "unspecified"))
      (node (ref "U16") (pin "2") (pinfunction "2_2") (pintype "unspecified"))
      (node (ref "U18") (pin "2") (pinfunction "2_2") (pintype "unspecified"))
      (node (ref "U2") (pin "5") (pinfunction "GND_5") (pintype "unspecified"))
      (node (ref "U3") (pin "10") (pinfunction "VSS_10") (pintype "unspecified"))
      (node (ref "U3") (pin "20") (pinfunction "VSSA/VREF-_20") (pintype "unspecified"))
      (node (ref "U3") (pin "27") (pinfunction "VSS_27") (pintype "unspecified"))
      (node (ref "U3") (pin "74") (pinfunction "VSS_74") (pintype "unspecified"))
      (node (ref "U3") (pin "99") (pinfunction "VSS_99") (pintype "unspecified"))
      (node (ref "U4") (pin "5") (pinfunction "GND_5") (pintype "unspecified"))
      (node (ref "U5") (pin "2") (pinfunction "D_2") (pintype "input"))
      (node (ref "U5") (pin "4") (pinfunction "D_4") (pintype "input"))
      (node (ref "U6") (pin "20") (pinfunction "AGND_20") (pintype "unspecified"))
      (node (ref "U6") (pin "23") (pinfunction "PGND_23") (pintype "unspecified"))
      (node (ref "U6") (pin "4") (pinfunction "DGND_4") (pintype "unspecified"))
      (node (ref "U7") (pin "2") (pinfunction "GND_2") (pintype "unspecified"))
      (node (ref "U8") (pin "2") (pinfunction "GND_2") (pintype "unspecified"))
      (node (ref "U9") (pin "1") (pinfunction "GND_1") (pintype "unspecified"))
      (node (ref "U9") (pin "5") (pinfunction "SDO_5") (pintype "unspecified"))
      (node (ref "U9") (pin "7") (pinfunction "GND_7") (pintype "unspecified"))
      (node (ref "USB1") (pin "25") (pinfunction "EH_25") (pintype "unspecified"))
      (node (ref "USB1") (pin "26") (pinfunction "EH_26") (pintype "unspecified"))
      (node (ref "USB1") (pin "27") (pinfunction "EH_27") (pintype "unspecified"))
      (node (ref "USB1") (pin "28") (pinfunction "EH_28") (pintype "unspecified"))
      (node (ref "USB1") (pin "A1") (pinfunction "GND_A1") (pintype "unspecified"))
      (node (ref "USB1") (pin "A12") (pinfunction "GND_A12") (pintype "unspecified"))
      (node (ref "USB1") (pin "B1") (pinfunction "GND_B1") (pintype "unspecified"))
      (node (ref "USB1") (pin "B12") (pinfunction "GND_B12") (pintype "unspecified"))
    )
    (net (code "61") (name "Net-(C11-Pad1)") (class "Default")
      (node (ref "C11") (pin "1") (pinfunction "1_1") (pintype "unspecified"))
      (node (ref "R14") (pin "2") (pinfunction "2_2") (pintype "unspecified"))
    )
    (net (code "62") (name "Net-(C17-Pad1)") (class "Default")
      (node (ref "C17") (pin "1") (pinfunction "1_1") (pintype "unspecified"))
      (node (ref "R21") (pin "2") (pinfunction "2_2") (pintype "unspecified"))
    )
    (net (code "63") (name "Net-(C22-Pad1)") (class "Default")
      (node (ref "C22") (pin "1") (pinfunction "1_1") (pintype "unspecified"))
      (node (ref "C23") (pin "1") (pinfunction "1_1") (pintype "unspecified"))
      (node (ref "R26") (pin "1") (pinfunction "1_1") (pintype "unspecified"))
    )
    (net (code "64") (name "Net-(C39-Pad1)") (class "Default")
      (node (ref "C39") (pin "1") (pinfunction "1_1") (pintype "unspecified"))
      (node (ref "L3") (pin "1") (pinfunction "1_1") (pintype "unspecified"))
    )
    (net (code "65") (name "Net-(C39-Pad2)") (class "Default")
      (node (ref "C39") (pin "2") (pinfunction "2_2") (pintype "unspecified"))
      (node (ref "L4") (pin "1") (pinfunction "1_1") (pintype "unspecified"))
    )
    (net (code "66") (name "Net-(D2-A)") (class "Default")
      (node (ref "C18") (pin "2") (pinfunction "2_2") (pintype "unspecified"))
      (node (ref "C20") (pin "2") (pinfunction "2_2") (pintype "unspecified"))
      (node (ref "D2") (pin "1") (pinfunction "A_1") (pintype "unspecified"))
      (node (ref "L2") (pin "2") (pinfunction "2_2") (pintype "unspecified"))
      (node (ref "R24") (pin "2") (pinfunction "2_2") (pintype "unspecified"))
    )
    (net (code "67") (name "Net-(J1-Pad2)") (class "Default")
      (node (ref "J1") (pin "2") (pinfunction "2_2") (pintype "unspecified"))
      (node (ref "Q2") (pin "3") (pinfunction "3_3") (pintype "input"))
    )
    (net (code "68") (name "Net-(LED1-Pad1)") (class "Default")
      (node (ref "LED1") (pin "1") (pinfunction "1_1") (pintype "unspecified"))
      (node (ref "R7") (pin "1") (pinfunction "1_1") (pintype "unspecified"))
    )
    (net (code "69") (name "Net-(LED2-Pad1)") (class "Default")
      (node (ref "LED2") (pin "1") (pinfunction "1_1") (pintype "unspecified"))
      (node (ref "R8") (pin "1") (pinfunction "1_1") (pintype "unspecified"))
    )
    (net (code "70") (name "Net-(Q2-Pad1)") (class "Default")
      (node (ref "Q2") (pin "1") (pinfunction "1_1") (pintype "input"))
      (node (ref "R4") (pin "2") (pinfunction "2_2") (pintype "unspecified"))
    )
    (net (code "71") (name "Net-(R13-Pad2)") (class "Default")
      (node (ref "R13") (pin "2") (pinfunction "2_2") (pintype "unspecified"))
      (node (ref "R15") (pin "2") (pinfunction "2_2") (pintype "unspecified"))
      (node (ref "R16") (pin "1") (pinfunction "1_1") (pintype "unspecified"))
    )
    (net (code "72") (name "Net-(R20-Pad2)") (class "Default")
      (node (ref "R20") (pin "2") (pinfunction "2_2") (pintype "unspecified"))
      (node (ref "R22") (pin "2") (pinfunction "2_2") (pintype "unspecified"))
      (node (ref "R24") (pin "1") (pinfunction "1_1") (pintype "unspecified"))
    )
    (net (code "73") (name "Net-(U2-BST)") (class "Default")
      (node (ref "R14") (pin "1") (pinfunction "1_1") (pintype "unspecified"))
      (node (ref "U2") (pin "4") (pinfunction "BST_4") (pintype "unspecified"))
    )
    (net (code "74") (name "Net-(U2-EN)") (class "Default")
      (node (ref "R9") (pin "1") (pinfunction "1_1") (pintype "unspecified"))
      (node (ref "U2") (pin "3") (pinfunction "EN_3") (pintype "unspecified"))
    )
    (net (code "75") (name "Net-(U2-FB)") (class "Default")
      (node (ref "R13") (pin "1") (pinfunction "1_1") (pintype "unspecified"))
      (node (ref "U2") (pin "1") (pinfunction "FB_1") (pintype "unspecified"))
    )
    (net (code "76") (name "Net-(U2-PG)") (class "Default")
      (node (ref "R10") (pin "2") (pinfunction "2_2") (pintype "unspecified"))
      (node (ref "U2") (pin "8") (pinfunction "PG_8") (pintype "unspecified"))
    )
    (net (code "77") (name "Net-(U2-SW)") (class "Default")
      (node (ref "C11") (pin "2") (pinfunction "2_2") (pintype "unspecified"))
      (node (ref "L1") (pin "1") (pinfunction "1_1") (pintype "unspecified"))
      (node (ref "U2") (pin "6") (pinfunction "SW_6") (pintype "unspecified"))
    )
    (net (code "78") (name "Net-(U2-VCC)") (class "Default")
      (node (ref "C10") (pin "2") (pinfunction "2_2") (pintype "unspecified"))
      (node (ref "R10") (pin "1") (pinfunction "1_1") (pintype "unspecified"))
      (node (ref "U2") (pin "2") (pinfunction "VCC_2") (pintype "unspecified"))
    )
    (net (code "79") (name "Net-(U3-NRST)") (class "Default")
      (node (ref "R11") (pin "1") (pinfunction "1_1") (pintype "unspecified"))
      (node (ref "U3") (pin "14") (pinfunction "NRST_14") (pintype "unspecified"))
    )
    (net (code "80") (name "Net-(U3-PB2{slash}BOOT1)") (class "Default")
      (node (ref "R12") (pin "2") (pinfunction "2_2") (pintype "unspecified"))
      (node (ref "U3") (pin "37") (pinfunction "PB2/BOOT1_37") (pintype "unspecified"))
    )
    (net (code "81") (name "Net-(U4-BST)") (class "Default")
      (node (ref "R21") (pin "1") (pinfunction "1_1") (pintype "unspecified"))
      (node (ref "U4") (pin "4") (pinfunction "BST_4") (pintype "unspecified"))
    )
    (net (code "82") (name "Net-(U4-EN)") (class "Default")
      (node (ref "R17") (pin "1") (pinfunction "1_1") (pintype "unspecified"))
      (node (ref "U4") (pin "3") (pinfunction "EN_3") (pintype "unspecified"))
    )
    (net (code "83") (name "Net-(U4-FB)") (class "Default")
      (node (ref "R20") (pin "1") (pinfunction "1_1") (pintype "unspecified"))
      (node (ref "U4") (pin "1") (pinfunction "FB_1") (pintype "unspecified"))
    )
    (net (code "84") (name "Net-(U4-PG)") (class "Default")
      (node (ref "R18") (pin "2") (pinfunction "2_2") (pintype "unspecified"))
      (node (ref "U4") (pin "8") (pinfunction "PG_8") (pintype "unspecified"))
    )
    (net (code "85") (name "Net-(U4-SW)") (class "Default")
      (node (ref "C17") (pin "2") (pinfunction "2_2") (pintype "unspecified"))
      (node (ref "L2") (pin "1") (pinfunction "1_1") (pintype "unspecified"))
      (node (ref "U4") (pin "6") (pinfunction "SW_6") (pintype "unspecified"))
    )
    (net (code "86") (name "Net-(U4-VCC)") (class "Default")
      (node (ref "C16") (pin "2") (pinfunction "2_2") (pintype "unspecified"))
      (node (ref "R18") (pin "1") (pinfunction "1_1") (pintype "unspecified"))
      (node (ref "U4") (pin "2") (pinfunction "VCC_2") (pintype "unspecified"))
    )
    (net (code "87") (name "Net-(U5-OSC1)") (class "Default")
      (node (ref "U5") (pin "1") (pinfunction "OSC1_1") (pintype "input"))
      (node (ref "U6") (pin "5") (pinfunction "CLKIN_5") (pintype "unspecified"))
    )
    (net (code "88") (name "Net-(U5-OSC2)") (class "Default")
      (node (ref "U5") (pin "3") (pinfunction "OSC2_3") (pintype "input"))
      (node (ref "U6") (pin "6") (pinfunction "XFB_6") (pintype "unspecified"))
    )
    (net (code "89") (name "Net-(U6-RESET)") (class "Default")
      (node (ref "R25") (pin "1") (pinfunction "1_1") (pintype "unspecified"))
      (node (ref "U6") (pin "19") (pinfunction "RESET_19") (pintype "unspecified"))
    )
    (net (code "90") (name "Net-(U6-SAG)") (class "Default")
      (node (ref "C23") (pin "2") (pinfunction "2_2") (pintype "unspecified"))
      (node (ref "U6") (pin "25") (pinfunction "SAG_25") (pintype "unspecified"))
    )
    (net (code "91") (name "Net-(U6-VIN)") (class "Default")
      (node (ref "C21") (pin "1") (pinfunction "1_1") (pintype "unspecified"))
      (node (ref "U6") (pin "22") (pinfunction "VIN_22") (pintype "unspecified"))
    )
    (net (code "92") (name "Net-(U6-VOUT)") (class "Default")
      (node (ref "C22") (pin "2") (pinfunction "2_2") (pintype "unspecified"))
      (node (ref "U6") (pin "26") (pinfunction "VOUT_26") (pintype "unspecified"))
    )
    (net (code "93") (name "Net-(U12-RF_IN)") (class "Default")
      (node (ref "U12") (pin "11") (pinfunction "RF_IN_11") (pintype "unspecified"))
      (node (ref "U13") (pin "6") (pinfunction "RFOUT_6") (pintype "unspecified"))
    )
    (net (code "94") (name "Net-(U13-RFIN)") (class "Default")
      (node (ref "L3") (pin "2") (pinfunction "2_2") (pintype "unspecified"))
      (node (ref "U13") (pin "3") (pinfunction "RFIN_3") (pintype "unspecified"))
    )
    (net (code "95") (name "Net-(U15-C1)") (class "Default")
      (node (ref "U15") (pin "10") (pinfunction "C1_10") (pintype "unspecified"))
      (node (ref "U18") (pin "1") (pinfunction "1_1") (pintype "unspecified"))
    )
    (net (code "96") (name "Net-(U15-SETC)") (class "Default")
      (node (ref "U15") (pin "12") (pinfunction "SETC_12") (pintype "unspecified"))
      (node (ref "U17") (pin "1") (pinfunction "1_1") (pintype "unspecified"))
    )
    (net (code "97") (name "Net-(U15-SETP)") (class "Default")
      (node (ref "U15") (pin "8") (pinfunction "SETP_8") (pintype "unspecified"))
      (node (ref "U17") (pin "2") (pinfunction "2_2") (pintype "unspecified"))
    )
    (net (code "98") (name "VBAT+") (class "Default")
      (node (ref "C14") (pin "2") (pinfunction "2_2") (pintype "unspecified"))
      (node (ref "C15") (pin "2") (pinfunction "2_2") (pintype "unspecified"))
      (node (ref "C8") (pin "2") (pinfunction "2_2") (pintype "unspecified"))
      (node (ref "C9") (pin "2") (pinfunction "2_2") (pintype "unspecified"))
      (node (ref "CN1") (pin "2") (pinfunction "2_2") (pintype "unspecified"))
      (node (ref "CN2") (pin "2") (pinfunction "2_2") (pintype "unspecified"))
      (node (ref "R1") (pin "2") (pinfunction "2_2") (pintype "unspecified"))
      (node (ref "R17") (pin "2") (pinfunction "2_2") (pintype "unspecified"))
      (node (ref "R9") (pin "2") (pinfunction "2_2") (pintype "unspecified"))
      (node (ref "U12") (pin "6") (pinfunction "VBAT_6") (pintype "unspecified"))
      (node (ref "U2") (pin "7") (pinfunction "IN_7") (pintype "unspecified"))
      (node (ref "U4") (pin "7") (pinfunction "IN_7") (pintype "unspecified"))
    )
    (net (code "99") (name "VDD") (class "Default")
      (node (ref "C2") (pin "2") (pinfunction "2_2") (pintype "unspecified"))
      (node (ref "C3") (pin "2") (pinfunction "2_2") (pintype "unspecified"))
      (node (ref "C30") (pin "2") (pinfunction "2_2") (pintype "unspecified"))
      (node (ref "C32") (pin "2") (pinfunction "2_2") (pintype "unspecified"))
      (node (ref "C33") (pin "2") (pinfunction "2_2") (pintype "unspecified"))
      (node (ref "C35") (pin "1") (pinfunction "1_1") (pintype "unspecified"))
      (node (ref "C4") (pin "2") (pinfunction "2_2") (pintype "unspecified"))
      (node (ref "C5") (pin "2") (pinfunction "2_2") (pintype "unspecified"))
      (node (ref "C6") (pin "2") (pinfunction "2_2") (pintype "unspecified"))
      (node (ref "C7") (pin "2") (pinfunction "2_2") (pintype "unspecified"))
      (node (ref "H6") (pin "1") (pinfunction "1_1") (pintype "unspecified"))
      (node (ref "R11") (pin "2") (pinfunction "2_2") (pintype "unspecified"))
      (node (ref "R28") (pin "2") (pinfunction "2_2") (pintype "unspecified"))
      (node (ref "R29") (pin "2") (pinfunction "2_2") (pintype "unspecified"))
      (node (ref "R3") (pin "2") (pinfunction "2_2") (pintype "unspecified"))
      (node (ref "SW1") (pin "1") (pinfunction "1_1") (pintype "unspecified"))
      (node (ref "SW1") (pin "3") (pinfunction "3_3") (pintype "unspecified"))
      (node (ref "U10") (pin "3") (pinfunction "#WP/IO2_3") (pintype "unspecified"))
      (node (ref "U10") (pin "7") (pinfunction "#HOLD/IO3_7") (pintype "unspecified"))
      (node (ref "U10") (pin "8") (pinfunction "VCC_8") (pintype "unspecified"))
      (node (ref "U3") (pin "100") (pinfunction "VDD_100") (pintype "unspecified"))
      (node (ref "U3") (pin "11") (pinfunction "VDD_11") (pintype "unspecified"))
      (node (ref "U3") (pin "21") (pinfunction "VREF+_21") (pintype "unspecified"))
      (node (ref "U3") (pin "22") (pinfunction "VDDA_22") (pintype "unspecified"))
      (node (ref "U3") (pin "28") (pinfunction "VDD_28") (pintype "unspecified"))
      (node (ref "U3") (pin "50") (pinfunction "VDD_50") (pintype "unspecified"))
      (node (ref "U3") (pin "6") (pinfunction "VBAT_6") (pintype "unspecified"))
      (node (ref "U3") (pin "75") (pinfunction "VDD_75") (pintype "unspecified"))
      (node (ref "U7") (pin "5") (pinfunction "VOUT_5") (pintype "unspecified"))
      (node (ref "U9") (pin "2") (pinfunction "CSB_2") (pintype "unspecified"))
      (node (ref "U9") (pin "6") (pinfunction "VDDIO_6") (pintype "unspecified"))
      (node (ref "U9") (pin "8") (pinfunction "VDD_8") (pintype "unspecified"))
    )
    (net (code "100") (name "unconnected-(CN1-Pad7)") (class "Default")
      (node (ref "CN1") (pin "7") (pinfunction "7_7") (pintype "unspecified+no_connect"))
    )
    (net (code "101") (name "unconnected-(CN1-Pad8)") (class "Default")
      (node (ref "CN1") (pin "8") (pinfunction "8_8") (pintype "unspecified+no_connect"))
    )
    (net (code "102") (name "unconnected-(CN2-Pad7)") (class "Default")
      (node (ref "CN2") (pin "7") (pinfunction "7_7") (pintype "unspecified+no_connect"))
    )
    (net (code "103") (name "unconnected-(SDO1-RESV-Pad2)") (class "Default")
      (node (ref "SDO1") (pin "2") (pinfunction "RESV_2") (pintype "unspecified+no_connect"))
    )
    (net (code "104") (name "unconnected-(SDO1-RESV-Pad3)") (class "Default")
      (node (ref "SDO1") (pin "3") (pinfunction "RESV_3") (pintype "unspecified+no_connect"))
    )
    (net (code "105") (name "unconnected-(SDO1-RESV-Pad10)") (class "Default")
      (node (ref "SDO1") (pin "10") (pinfunction "RESV_10") (pintype "unspecified+no_connect"))
    )
    (net (code "106") (name "unconnected-(SDO1-RESV-Pad11)") (class "Default")
      (node (ref "SDO1") (pin "11") (pinfunction "RESV_11") (pintype "unspecified+no_connect"))
    )
    (net (code "107") (name "unconnected-(U3-NC-Pad19)") (class "Default")
      (node (ref "U3") (pin "19") (pinfunction "NC_19") (pintype "unspecified+no_connect"))
    )
    (net (code "108") (name "unconnected-(U3-PA8-Pad67)") (class "Default")
      (node (ref "U3") (pin "67") (pinfunction "PA8_67") (pintype "unspecified+no_connect"))
    )
    (net (code "109") (name "unconnected-(U3-PB4-Pad90)") (class "Default")
      (node (ref "U3") (pin "90") (pinfunction "PB4_90") (pintype "unspecified+no_connect"))
    )
    (net (code "110") (name "unconnected-(U3-PB5-Pad91)") (class "Default")
      (node (ref "U3") (pin "91") (pinfunction "PB5_91") (pintype "unspecified+no_connect"))
    )
    (net (code "111") (name "unconnected-(U3-PB12-Pad51)") (class "Default")
      (node (ref "U3") (pin "51") (pinfunction "PB12_51") (pintype "unspecified+no_connect"))
    )
    (net (code "112") (name "unconnected-(U3-PB13-Pad52)") (class "Default")
      (node (ref "U3") (pin "52") (pinfunction "PB13_52") (pintype "unspecified+no_connect"))
    )
    (net (code "113") (name "unconnected-(U3-PB14-Pad53)") (class "Default")
      (node (ref "U3") (pin "53") (pinfunction "PB14_53") (pintype "unspecified+no_connect"))
    )
    (net (code "114") (name "unconnected-(U3-PB15-Pad54)") (class "Default")
      (node (ref "U3") (pin "54") (pinfunction "PB15_54") (pintype "unspecified+no_connect"))
    )
    (net (code "115") (name "unconnected-(U3-PC13-Pad7)") (class "Default")
      (node (ref "U3") (pin "7") (pinfunction "PC13_7") (pintype "unspecified+no_connect"))
    )
    (net (code "116") (name "unconnected-(U3-PC14-Pad8)") (class "Default")
      (node (ref "U3") (pin "8") (pinfunction "PC14_8") (pintype "unspecified+no_connect"))
    )
    (net (code "117") (name "unconnected-(U3-PC15-Pad9)") (class "Default")
      (node (ref "U3") (pin "9") (pinfunction "PC15_9") (pintype "unspecified+no_connect"))
    )
    (net (code "118") (name "unconnected-(U3-PD0-Pad81)") (class "Default")
      (node (ref "U3") (pin "81") (pinfunction "PD0_81") (pintype "unspecified+no_connect"))
    )
    (net (code "119") (name "unconnected-(U3-PD2-Pad83)") (class "Default")
      (node (ref "U3") (pin "83") (pinfunction "PD2_83") (pintype "unspecified+no_connect"))
    )
    (net (code "120") (name "unconnected-(U3-PD7-Pad88)") (class "Default")
      (node (ref "U3") (pin "88") (pinfunction "PD7_88") (pintype "unspecified+no_connect"))
    )
    (net (code "121") (name "unconnected-(U3-PD8-Pad55)") (class "Default")
      (node (ref "U3") (pin "55") (pinfunction "PD8_55") (pintype "unspecified+no_connect"))
    )
    (net (code "122") (name "unconnected-(U3-PD9-Pad56)") (class "Default")
      (node (ref "U3") (pin "56") (pinfunction "PD9_56") (pintype "unspecified+no_connect"))
    )
    (net (code "123") (name "unconnected-(U3-PD10-Pad57)") (class "Default")
      (node (ref "U3") (pin "57") (pinfunction "PD10_57") (pintype "unspecified+no_connect"))
    )
    (net (code "124") (name "unconnected-(U3-PD11-Pad58)") (class "Default")
      (node (ref "U3") (pin "58") (pinfunction "PD11_58") (pintype "unspecified+no_connect"))
    )
    (net (code "125") (name "unconnected-(U3-PD12-Pad59)") (class "Default")
      (node (ref "U3") (pin "59") (pinfunction "PD12_59") (pintype "unspecified+no_connect"))
    )
    (net (code "126") (name "unconnected-(U3-PE0-Pad97)") (class "Default")
      (node (ref "U3") (pin "97") (pinfunction "PE0_97") (pintype "unspecified+no_connect"))
    )
    (net (code "127") (name "unconnected-(U3-PE1-Pad98)") (class "Default")
      (node (ref "U3") (pin "98") (pinfunction "PE1_98") (pintype "unspecified+no_connect"))
    )
    (net (code "128") (name "unconnected-(U3-PE2-Pad1)") (class "Default")
      (node (ref "U3") (pin "1") (pinfunction "PE2_1") (pintype "unspecified+no_connect"))
    )
    (net (code "129") (name "unconnected-(U3-PE3-Pad2)") (class "Default")
      (node (ref "U3") (pin "2") (pinfunction "PE3_2") (pintype "unspecified+no_connect"))
    )
    (net (code "130") (name "unconnected-(U3-PE4-Pad3)") (class "Default")
      (node (ref "U3") (pin "3") (pinfunction "PE4_3") (pintype "unspecified+no_connect"))
    )
    (net (code "131") (name "unconnected-(U3-PE5-Pad4)") (class "Default")
      (node (ref "U3") (pin "4") (pinfunction "PE5_4") (pintype "unspecified+no_connect"))
    )
    (net (code "132") (name "unconnected-(U3-PE6-Pad5)") (class "Default")
      (node (ref "U3") (pin "5") (pinfunction "PE6_5") (pintype "unspecified+no_connect"))
    )
    (net (code "133") (name "unconnected-(U3-PE7-Pad38)") (class "Default")
      (node (ref "U3") (pin "38") (pinfunction "PE7_38") (pintype "unspecified+no_connect"))
    )
    (net (code "134") (name "unconnected-(U3-PE8-Pad39)") (class "Default")
      (node (ref "U3") (pin "39") (pinfunction "PE8_39") (pintype "unspecified+no_connect"))
    )
    (net (code "135") (name "unconnected-(U3-PE9-Pad40)") (class "Default")
      (node (ref "U3") (pin "40") (pinfunction "PE9_40") (pintype "unspecified+no_connect"))
    )
    (net (code "136") (name "unconnected-(U3-PE10-Pad41)") (class "Default")
      (node (ref "U3") (pin "41") (pinfunction "PE10_41") (pintype "unspecified+no_connect"))
    )
    (net (code "137") (name "unconnected-(U3-PE11-Pad42)") (class "Default")
      (node (ref "U3") (pin "42") (pinfunction "PE11_42") (pintype "unspecified+no_connect"))
    )
    (net (code "138") (name "unconnected-(U3-PE12-Pad43)") (class "Default")
      (node (ref "U3") (pin "43") (pinfunction "PE12_43") (pintype "unspecified+no_connect"))
    )
    (net (code "139") (name "unconnected-(U3-PE13-Pad44)") (class "Default")
      (node (ref "U3") (pin "44") (pinfunction "PE13_44") (pintype "unspecified+no_connect"))
    )
    (net (code "140") (name "unconnected-(U3-PE14-Pad45)") (class "Default")
      (node (ref "U3") (pin "45") (pinfunction "PE14_45") (pintype "unspecified+no_connect"))
    )
    (net (code "141") (name "unconnected-(U3-PE15-Pad46)") (class "Default")
      (node (ref "U3") (pin "46") (pinfunction "PE15_46") (pintype "unspecified+no_connect"))
    )
    (net (code "142") (name "unconnected-(U3-PH3-Pad49)") (class "Default")
      (node (ref "U3") (pin "49") (pinfunction "PH3_49") (pintype "unspecified+no_connect"))
    )
    (net (code "143") (name "unconnected-(U6-CLKOUT-Pad7)") (class "Default")
      (node (ref "U6") (pin "7") (pinfunction "CLKOUT_7") (pintype "unspecified+no_connect"))
    )
    (net (code "144") (name "unconnected-(U6-HSYNC-Pad18)") (class "Default")
      (node (ref "U6") (pin "18") (pinfunction "HSYNC_18") (pintype "unspecified+no_connect"))
    )
    (net (code "145") (name "unconnected-(U6-LOS-Pad12)") (class "Default")
      (node (ref "U6") (pin "12") (pinfunction "LOS_12") (pintype "unspecified+no_connect"))
    )
    (net (code "146") (name "unconnected-(U6-NC-Pad1)") (class "Default")
      (node (ref "U6") (pin "1") (pinfunction "NC_1") (pintype "unspecified+no_connect"))
    )
    (net (code "147") (name "unconnected-(U6-NC-Pad2)") (class "Default")
      (node (ref "U6") (pin "2") (pinfunction "NC_2") (pintype "unspecified+no_connect"))
    )
    (net (code "148") (name "unconnected-(U6-NC-Pad13)") (class "Default")
      (node (ref "U6") (pin "13") (pinfunction "NC_13") (pintype "unspecified+no_connect"))
    )
    (net (code "149") (name "unconnected-(U6-NC-Pad14)") (class "Default")
      (node (ref "U6") (pin "14") (pinfunction "NC_14") (pintype "unspecified+no_connect"))
    )
    (net (code "150") (name "unconnected-(U6-NC-Pad15)") (class "Default")
      (node (ref "U6") (pin "15") (pinfunction "NC_15") (pintype "unspecified+no_connect"))
    )
    (net (code "151") (name "unconnected-(U6-NC-Pad16)") (class "Default")
      (node (ref "U6") (pin "16") (pinfunction "NC_16") (pintype "unspecified+no_connect"))
    )
    (net (code "152") (name "unconnected-(U6-NC-Pad27)") (class "Default")
      (node (ref "U6") (pin "27") (pinfunction "NC_27") (pintype "unspecified+no_connect"))
    )
    (net (code "153") (name "unconnected-(U6-NC-Pad28)") (class "Default")
      (node (ref "U6") (pin "28") (pinfunction "NC_28") (pintype "unspecified+no_connect"))
    )
    (net (code "154") (name "unconnected-(U6-VSYNC-Pad17)") (class "Default")
      (node (ref "U6") (pin "17") (pinfunction "VSYNC_17") (pintype "unspecified+no_connect"))
    )
    (net (code "155") (name "unconnected-(U7-NC-Pad4)") (class "Default")
      (node (ref "U7") (pin "4") (pinfunction "NC_4") (pintype "unspecified+no_connect"))
    )
    (net (code "156") (name "unconnected-(U8-NC-Pad4)") (class "Default")
      (node (ref "U8") (pin "4") (pinfunction "NC_4") (pintype "unspecified+no_connect"))
    )
    (net (code "157") (name "unconnected-(U12-1PPS-Pad4)") (class "Default")
      (node (ref "U12") (pin "4") (pinfunction "1PPS_4") (pintype "unspecified+no_connect"))
    )
    (net (code "158") (name "unconnected-(U12-NC-Pad7)") (class "Default")
      (node (ref "U12") (pin "7") (pinfunction "NC_7") (pintype "unspecified+no_connect"))
    )
    (net (code "159") (name "unconnected-(U12-NC-Pad13)") (class "Default")
      (node (ref "U12") (pin "13") (pinfunction "NC_13") (pintype "unspecified+no_connect"))
    )
    (net (code "160") (name "unconnected-(U12-NRESET-Pad9)") (class "Default")
      (node (ref "U12") (pin "9") (pinfunction "NRESET_9") (pintype "unspecified+no_connect"))
    )
    (net (code "161") (name "unconnected-(U12-ON{slash}OFF-Pad5)") (class "Default")
      (node (ref "U12") (pin "5") (pinfunction "ON/OFF_5") (pintype "unspecified+no_connect"))
    )
    (net (code "162") (name "unconnected-(U12-Reserved-Pad15)") (class "Default")
      (node (ref "U12") (pin "15") (pinfunction "Reserved_15") (pintype "unspecified+no_connect"))
    )
    (net (code "163") (name "unconnected-(U12-Reserved-Pad18)") (class "Default")
      (node (ref "U12") (pin "18") (pinfunction "Reserved_18") (pintype "unspecified+no_connect"))
    )
    (net (code "164") (name "unconnected-(U12-SCL-Pad17)") (class "Default")
      (node (ref "U12") (pin "17") (pinfunction "SCL_17") (pintype "unspecified+no_connect"))
    )
    (net (code "165") (name "unconnected-(U12-SDA-Pad16)") (class "Default")
      (node (ref "U12") (pin "16") (pinfunction "SDA_16") (pintype "unspecified+no_connect"))
    )
    (net (code "166") (name "unconnected-(U12-VCC_RF-Pad14)") (class "Default")
      (node (ref "U12") (pin "14") (pinfunction "VCC_RF_14") (pintype "unspecified+no_connect"))
    )
    (net (code "167") (name "unconnected-(U15-DRDY-Pad15)") (class "Default")
      (node (ref "U15") (pin "15") (pinfunction "DRDY_15") (pintype "unspecified+no_connect"))
    )
    (net (code "168") (name "unconnected-(U15-NC-Pad3)") (class "Default")
      (node (ref "U15") (pin "3") (pinfunction "NC_3") (pintype "unspecified+no_connect"))
    )
    (net (code "169") (name "unconnected-(U15-NC-Pad5)") (class "Default")
      (node (ref "U15") (pin "5") (pinfunction "NC_5") (pintype "unspecified+no_connect"))
    )
    (net (code "170") (name "unconnected-(U15-NC-Pad6)") (class "Default")
      (node (ref "U15") (pin "6") (pinfunction "NC_6") (pintype "unspecified+no_connect"))
    )
    (net (code "171") (name "unconnected-(U15-NC-Pad7)") (class "Default")
      (node (ref "U15") (pin "7") (pinfunction "NC_7") (pintype "unspecified+no_connect"))
    )
    (net (code "172") (name "unconnected-(U15-NC-Pad14)") (class "Default")
      (node (ref "U15") (pin "14") (pinfunction "NC_14") (pintype "unspecified+no_connect"))
    )
    (net (code "173") (name "unconnected-(USB1-CC1-PadA5)") (class "Default")
      (node (ref "USB1") (pin "A5") (pinfunction "CC1_A5") (pintype "unspecified+no_connect"))
    )
    (net (code "174") (name "unconnected-(USB1-CC2-PadB5)") (class "Default")
      (node (ref "USB1") (pin "B5") (pinfunction "CC2_B5") (pintype "unspecified+no_connect"))
    )
    (net (code "175") (name "unconnected-(USB1-SUB1-PadA8)") (class "Default")
      (node (ref "USB1") (pin "A8") (pinfunction "SUB1_A8") (pintype "unspecified+no_connect"))
    )
    (net (code "176") (name "unconnected-(USB1-SUB2-PadB8)") (class "Default")
      (node (ref "USB1") (pin "B8") (pinfunction "SUB2_B8") (pintype "unspecified+no_connect"))
    )
  )
)
